# Sheet1.net
KiCad netlist of a schematic drawn in Altium Designer
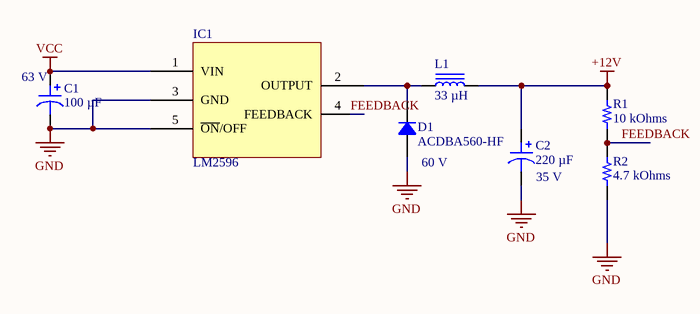
[diagram p0: Sheet1.SchDoc]

(export (version "E")
  (design (tool "Eeschema 10.0.6"))
  (components
    (comp (ref "C1")
      (value "100 µF")
      (footprint "CAP AL TH D8 L3.5 H12.5")
      (description "CAP ALUM 100UF 20% 63V RADIAL")
      (fields
        (field (name "PART NUMBER") "ECA-1JM101")
        (field (name "MANUFACTURER") "Panasonic Electronic Components")
        (field (name "VOLTAGE - RATED") "63 V")
      )
      (libsource (lib "Celestial Altium Library - altium_library (2)") (part "Polarised Capacitor"))
    )
    (comp (ref "C2")
      (value "220 µF")
      (footprint "CAP AL TH D8 L3.5 H12.5")
      (description "CAP ALUM 220UF 20% 35V RADIAL")
      (fields
        (field (name "PART NUMBER") "ECA-1VM221BJ")
        (field (name "MANUFACTURER") "Panasonic Electronic Components")
        (field (name "VOLTAGE - RATED") "35 V")
      )
      (libsource (lib "Celestial Altium Library - altium_library (2)") (part "Polarised Capacitor"))
    )
    (comp (ref "D1")
      (value "ACDBA560-HF")
      (footprint "DO214AC SMA")
      (description "DIODE SCHOTTKY 60V 5A DO214AC")
      (fields
        (field (name "MANUFACTURER") "Comchip Technology")
        (field (name "VOLTAGE - DC REVERSE (VR) (MAX)") "60 V")
      )
      (libsource (lib "Celestial Altium Library - altium_library (2)") (part "Diode"))
    )
    (comp (ref "IC1")
      (value "LM2596")
      (footprint "D2PACK:PCBComponent_1")
      (libsource (lib "LM2596") (part "LM2596"))
    )
    (comp (ref "L1")
      (value "33 µH")
      (footprint "BOURNS SRR1280")
      (description "FIXED IND 33UH 3.5A 57 MOHM SMD")
      (fields (field (name "PART NUMBER") "SRR1280-330M") (field (name "MANUFACTURER") "Bourns Inc."))
      (libsource (lib "Celestial Altium Library - altium_library (2)") (part "Inductor"))
    )
    (comp (ref "R1")
      (value "10 kOhms")
      (footprint "RES 0805_2012")
      (description "RES 10K OHM 0.1% 1/10W 0805")
      (fields
        (field (name "PART NUMBER") "RNCS0805BKE10K0")
        (field (name "MANUFACTURER") "Stackpole Electronics Inc")
      )
      (libsource (lib "Celestial Altium Library - altium_library (2)") (part "Resistor"))
    )
    (comp (ref "R2")
      (value "4.7 kOhms")
      (footprint "RES 0805_2012")
      (description "RES 4.7K OHM 1% 1/8W 0805")
      (fields (field (name "PART NUMBER") "RC0805FR-074K7P") (field (name "MANUFACTURER") "Yageo"))
      (libsource (lib "Celestial Altium Library - altium_library (2)") (part "Resistor"))
    )
  )
  (nets
    (net (code "1") (name "+12V") (class "Default")
      (node (ref "C2") (pin "1") (pinfunction "1_1") (pintype "passive"))
      (node (ref "L1") (pin "2") (pinfunction "2_2") (pintype "passive"))
      (node (ref "R1") (pin "2") (pinfunction "2_2") (pintype "passive"))
    )
    (net (code "2") (name "/FEEDBACK") (class "Default")
      (node (ref "IC1") (pin "4") (pinfunction "FEEDBACK_4") (pintype "passive"))
      (node (ref "R1") (pin "1") (pinfunction "1_1") (pintype "passive"))
      (node (ref "R2") (pin "2") (pinfunction "2_2") (pintype "passive"))
    )
    (net (code "3") (name "GND") (class "Default")
      (node (ref "C1") (pin "2") (pinfunction "2_2") (pintype "passive"))
      (node (ref "C2") (pin "2") (pinfunction "2_2") (pintype "passive"))
      (node (ref "D1") (pin "1") (pinfunction "1_1") (pintype "passive"))
      (node (ref "IC1") (pin "3") (pinfunction "GND_3") (pintype "passive"))
      (node (ref "IC1") (pin "5") (pinfunction "~{ON}/OFF_5") (pintype "passive"))
      (node (ref "R2") (pin "1") (pinfunction "1_1") (pintype "passive"))
    )
    (net (code "4") (name "Net-(IC1-OUTPUT)") (class "Default")
      (node (ref "D1") (pin "2") (pinfunction "2_2") (pintype "passive"))
      (node (ref "IC1") (pin "2") (pinfunction "OUTPUT_2") (pintype "passive"))
      (node (ref "L1") (pin "1") (pinfunction "1_1") (pintype "passive"))
    )
    (net (code "5") (name "VCC") (class "Default")
      (node (ref "C1") (pin "1") (pinfunction "1_1") (pintype "passive"))
      (node (ref "IC1") (pin "1") (pinfunction "VIN_1") (pintype "passive"))
    )
  )
)
